# Sheet2.net
KiCad netlist of a schematic drawn in Altium Designer
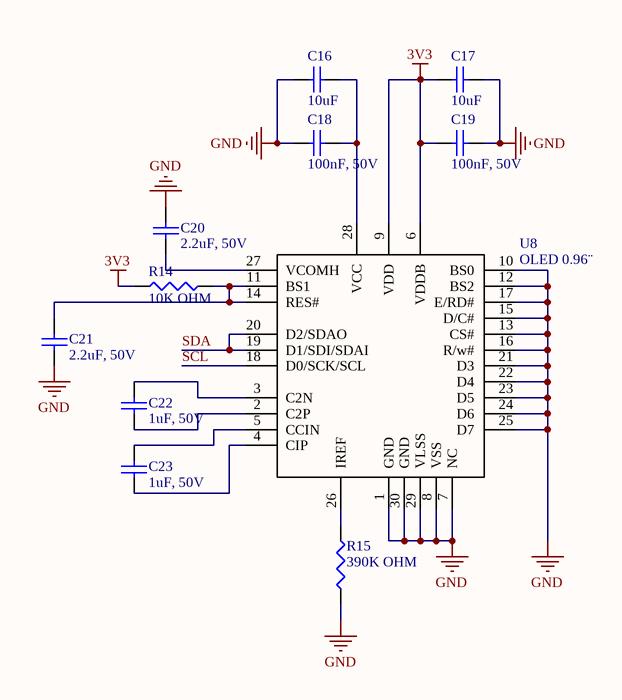
[diagram p0: Sheet2.SchDoc]

(export (version "E")
  (design (tool "Eeschema 10.0.6"))
  (components
    (comp (ref "C16")
      (value "10uF")
      (footprint "CAP0805")
      (description "CAP CER 10UF 0805")
      (fields
        (field (name "MANUFACTURER") "Samsung Electro-Mechanics")
        (field (name "MANUFACTURER PART NUMBER") "CL05B104KB5NNNC")
      )
      (libsource (lib "Schlib1") (part "C0805_10UF"))
    )
    (comp (ref "C17")
      (value "10uF")
      (footprint "CAP0805")
      (description "CAP CER 10UF 0805")
      (fields
        (field (name "MANUFACTURER") "Samsung Electro-Mechanics")
        (field (name "MANUFACTURER PART NUMBER") "CL05B104KB5NNNC")
      )
      (libsource (lib "Schlib1") (part "C0805_10UF"))
    )
    (comp (ref "C18")
      (value "100nF, 50V")
      (footprint "CAP0805")
      (description "CAP CER 0.1UF 0805")
      (fields
        (field (name "MANUFACTURER") "Samsung Electro-Mechanics")
        (field (name "MANUFACTURER PART NUMBER") "CL05B104KB5NNNC")
      )
      (libsource (lib "Schlib1") (part "C0805 100nF"))
    )
    (comp (ref "C19")
      (value "100nF, 50V")
      (footprint "CAP0805")
      (description "CAP CER 0.1UF 0805")
      (fields
        (field (name "MANUFACTURER") "Samsung Electro-Mechanics")
        (field (name "MANUFACTURER PART NUMBER") "CL05B104KB5NNNC")
      )
      (libsource (lib "Schlib1") (part "C0805 100nF"))
    )
    (comp (ref "C20")
      (value "2.2uF, 50V")
      (footprint "CAP0805")
      (description "CAP CER 2.2UF 0805")
      (fields
        (field (name "MANUFACTURER") "Samsung Electro-Mechanics")
        (field (name "MANUFACTURER PART NUMBER") "CL05B104KB5NNNC")
      )
      (libsource (lib "Schlib1") (part "C0805 2.2uF"))
    )
    (comp (ref "C21")
      (value "2.2uF, 50V")
      (footprint "CAP0805")
      (description "CAP CER 2.2UF 0805")
      (fields
        (field (name "MANUFACTURER") "Samsung Electro-Mechanics")
        (field (name "MANUFACTURER PART NUMBER") "CL05B104KB5NNNC")
      )
      (libsource (lib "Schlib1") (part "C0805 2.2uF"))
    )
    (comp (ref "C22")
      (value "1uF, 50V")
      (footprint "CAP0805")
      (description "CAP CER 1UF 0805")
      (fields
        (field (name "MANUFACTURER") "Samsung Electro-Mechanics")
        (field (name "MANUFACTURER PART NUMBER") "CL05B104KB5NNNC")
      )
      (libsource (lib "Schlib1") (part "C0805 1uF"))
    )
    (comp (ref "C23")
      (value "1uF, 50V")
      (footprint "CAP0805")
      (description "CAP CER 1UF 0805")
      (fields
        (field (name "MANUFACTURER") "Samsung Electro-Mechanics")
        (field (name "MANUFACTURER PART NUMBER") "CL05B104KB5NNNC")
      )
      (libsource (lib "Schlib1") (part "C0805 1uF"))
    )
    (comp (ref "R14")
      (value "10K OHM")
      (footprint "RES 0805")
      (description "RES 10K OHM 1% 1/16W 0805")
      (fields
        (field (name "MANUFACTURER") "Yageo Group")
        (field (name "MANUFACTURER PART NUMBER") "RC0402FR-074K7L")
      )
      (libsource (lib "Schlib1") (part "RES 10K OHM"))
    )
    (comp (ref "R15")
      (value "390K OHM")
      (footprint "RES 0805")
      (description "RES 390K OHM 1% 1/16W 0805")
      (fields
        (field (name "MANUFACTURER") "Yageo Group")
        (field (name "MANUFACTURER PART NUMBER") "RC0402FR-074K7L")
      )
      (libsource (lib "Schlib1") (part "RES 0805 390K OHM_1"))
    )
    (comp (ref "U8")
      (value "OLED 0.96¨")
      (footprint "OLED_0.96IN_WHITE_SSD1306")
      (description "By Prince")
      (libsource (lib "Schlib1") (part "OLED 0.96¨"))
    )
  )
  (nets
    (net (code "1") (name "/SCL") (class "Default")
      (node (ref "U8") (pin "18") (pinfunction "D0/SCK/SCL_18") (pintype "passive"))
    )
    (net (code "2") (name "/SDA") (class "Default")
      (node (ref "U8") (pin "19") (pinfunction "D1/SDI/SDAI_19") (pintype "passive"))
      (node (ref "U8") (pin "20") (pinfunction "D2/SDAO_20") (pintype "passive"))
    )
    (net (code "3") (name "3V3") (class "Default")
      (node (ref "C17") (pin "1") (pinfunction "1_1") (pintype "passive"))
      (node (ref "C19") (pin "1") (pinfunction "1_1") (pintype "passive"))
      (node (ref "R14") (pin "1") (pinfunction "1_1") (pintype "passive"))
      (node (ref "U8") (pin "6") (pinfunction "VDDB_6") (pintype "passive"))
      (node (ref "U8") (pin "9") (pinfunction "VDD_9") (pintype "passive"))
    )
    (net (code "4") (name "GND") (class "Default")
      (node (ref "C16") (pin "1") (pinfunction "1_1") (pintype "passive"))
      (node (ref "C17") (pin "2") (pinfunction "2_2") (pintype "passive"))
      (node (ref "C18") (pin "1") (pinfunction "1_1") (pintype "passive"))
      (node (ref "C19") (pin "2") (pinfunction "2_2") (pintype "passive"))
      (node (ref "C20") (pin "2") (pinfunction "2_2") (pintype "passive"))
      (node (ref "C21") (pin "2") (pinfunction "2_2") (pintype "passive"))
      (node (ref "R15") (pin "2") (pinfunction "2_2") (pintype "passive"))
      (node (ref "U8") (pin "1") (pinfunction "GND_1") (pintype "passive"))
      (node (ref "U8") (pin "10") (pinfunction "BS0_10") (pintype "passive"))
      (node (ref "U8") (pin "12") (pinfunction "BS2_12") (pintype "passive"))
      (node (ref "U8") (pin "13") (pinfunction "CS#_13") (pintype "passive"))
      (node (ref "U8") (pin "15") (pinfunction "D/C#_15") (pintype "passive"))
      (node (ref "U8") (pin "16") (pinfunction "R/w#_16") (pintype "passive"))
      (node (ref "U8") (pin "17") (pinfunction "E/RD#_17") (pintype "passive"))
      (node (ref "U8") (pin "21") (pinfunction "D3_21") (pintype "passive"))
      (node (ref "U8") (pin "22") (pinfunction "D4_22") (pintype "passive"))
      (node (ref "U8") (pin "23") (pinfunction "D5_23") (pintype "passive"))
      (node (ref "U8") (pin "24") (pinfunction "D6_24") (pintype "passive"))
      (node (ref "U8") (pin "25") (pinfunction "D7_25") (pintype "passive"))
      (node (ref "U8") (pin "29") (pinfunction "VLSS_29") (pintype "passive"))
      (node (ref "U8") (pin "30") (pinfunction "GND_30") (pintype "passive"))
      (node (ref "U8") (pin "7") (pinfunction "NC_7") (pintype "passive"))
      (node (ref "U8") (pin "8") (pinfunction "VSS_8") (pintype "passive"))
    )
    (net (code "5") (name "Net-(U8-BS1)") (class "Default")
      (node (ref "C21") (pin "1") (pinfunction "1_1") (pintype "passive"))
      (node (ref "R14") (pin "2") (pinfunction "2_2") (pintype "passive"))
      (node (ref "U8") (pin "11") (pinfunction "BS1_11") (pintype "passive"))
      (node (ref "U8") (pin "14") (pinfunction "RES#_14") (pintype "passive"))
    )
    (net (code "6") (name "Net-(U8-C2N)") (class "Default")
      (node (ref "C22") (pin "2") (pinfunction "2_2") (pintype "passive"))
      (node (ref "U8") (pin "3") (pinfunction "C2N_3") (pintype "passive"))
    )
    (net (code "7") (name "Net-(U8-C2P)") (class "Default")
      (node (ref "C22") (pin "1") (pinfunction "1_1") (pintype "passive"))
      (node (ref "U8") (pin "2") (pinfunction "C2P_2") (pintype "passive"))
    )
    (net (code "8") (name "Net-(U8-CCIN)") (class "Default")
      (node (ref "C23") (pin "2") (pinfunction "2_2") (pintype "passive"))
      (node (ref "U8") (pin "5") (pinfunction "CCIN_5") (pintype "passive"))
    )
    (net (code "9") (name "Net-(U8-CIP)") (class "Default")
      (node (ref "C23") (pin "1") (pinfunction "1_1") (pintype "passive"))
      (node (ref "U8") (pin "4") (pinfunction "CIP_4") (pintype "passive"))
    )
    (net (code "10") (name "Net-(U8-IREF)") (class "Default")
      (node (ref "R15") (pin "1") (pinfunction "1_1") (pintype "passive"))
      (node (ref "U8") (pin "26") (pinfunction "IREF_26") (pintype "passive"))
    )
    (net (code "11") (name "Net-(U8-VCC)") (class "Default")
      (node (ref "C16") (pin "2") (pinfunction "2_2") (pintype "passive"))
      (node (ref "C18") (pin "2") (pinfunction "2_2") (pintype "passive"))
      (node (ref "U8") (pin "28") (pinfunction "VCC_28") (pintype "passive"))
    )
    (net (code "12") (name "Net-(U8-VCOMH)") (class "Default")
      (node (ref "C20") (pin "1") (pinfunction "1_1") (pintype "passive"))
      (node (ref "U8") (pin "27") (pinfunction "VCOMH_27") (pintype "passive"))
    )
  )
)
